# Schematico.net
KiCad netlist of a schematic drawn in EAGLE
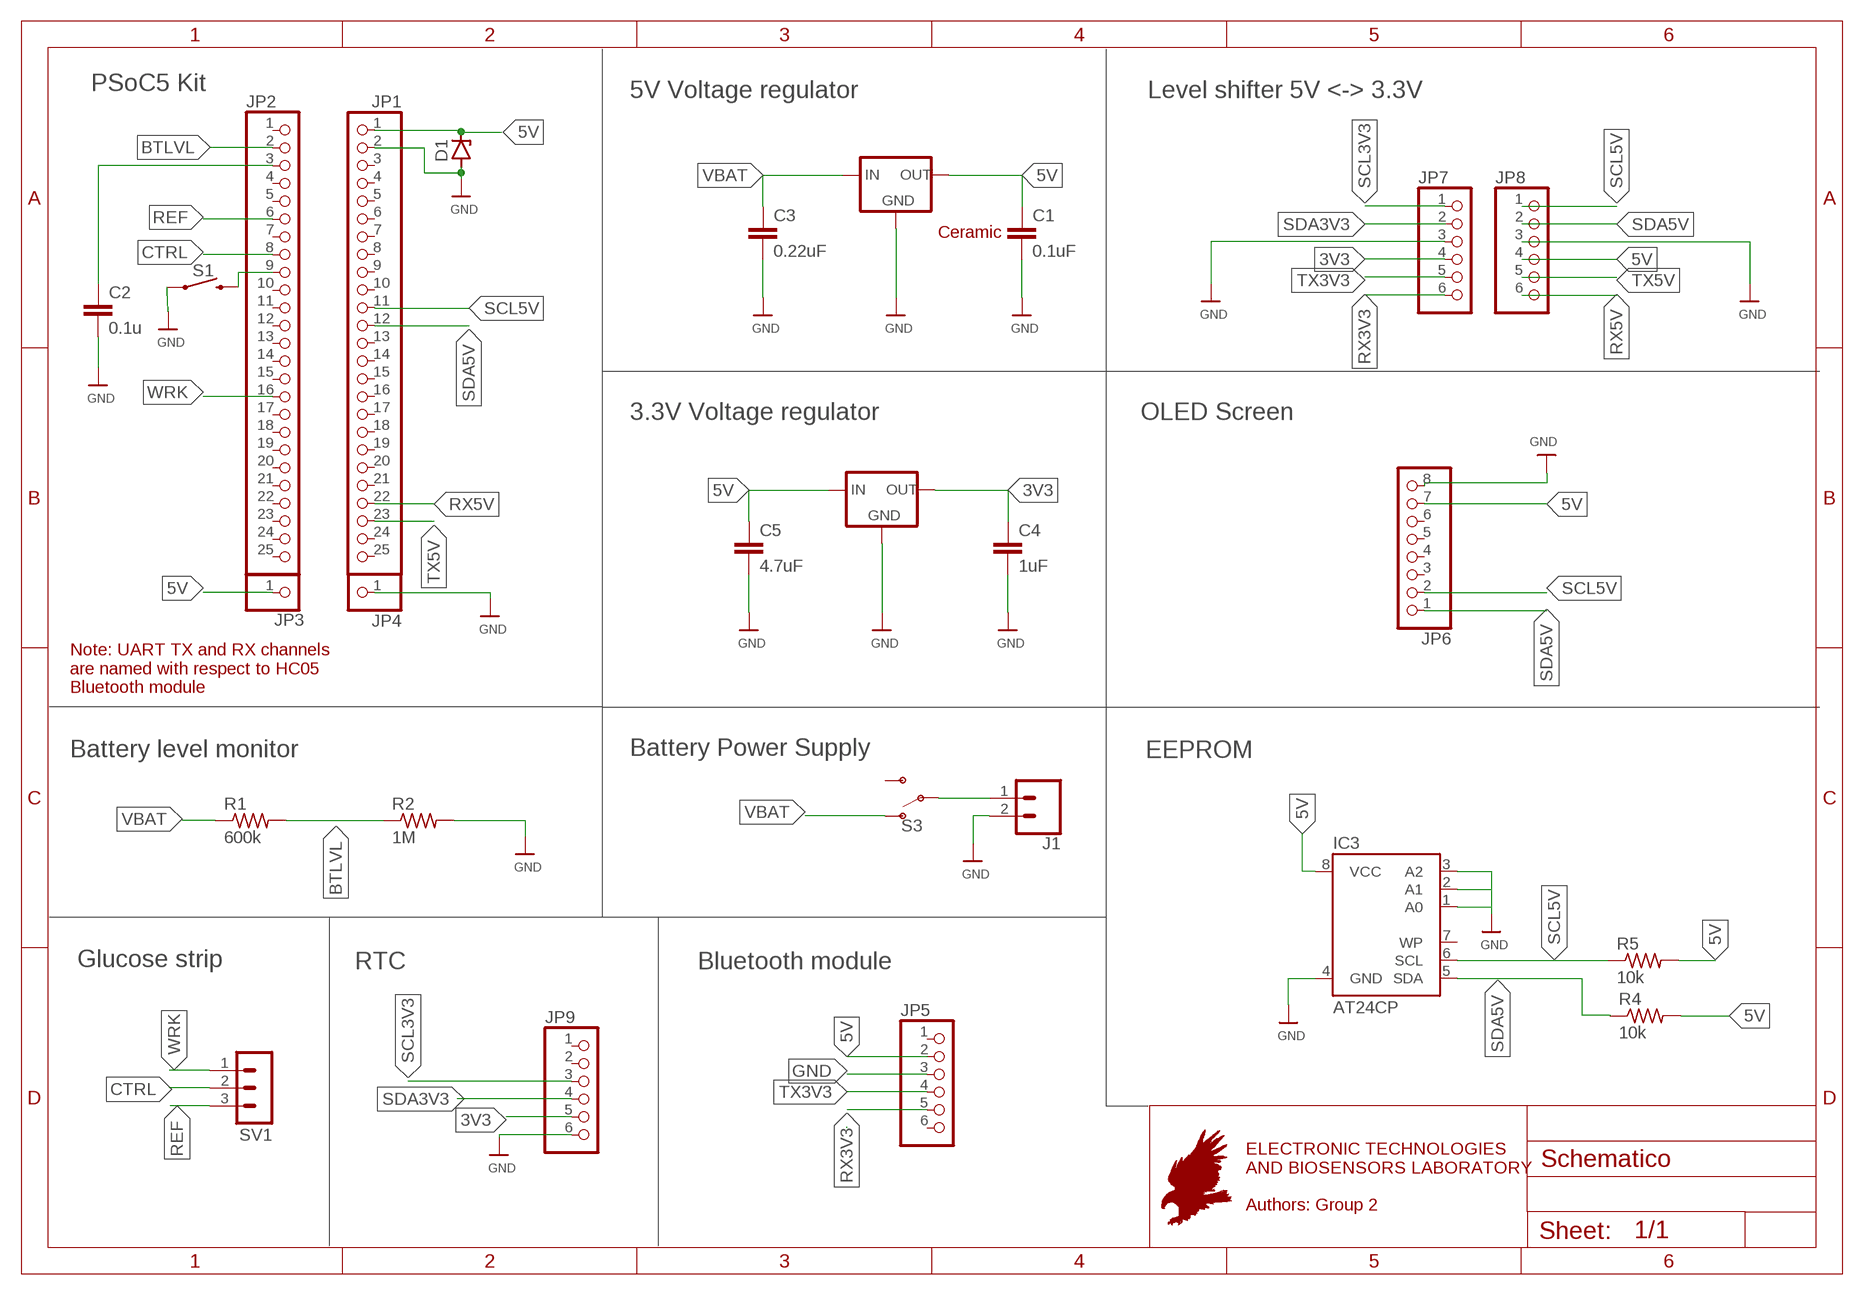
[diagram p0: schematic, sheet 1]

(export (version "E")
  (design (tool "Eeschema 10.0.6"))
  (components
    (comp (ref "C1")
      (value "0.1uF")
      (footprint "eagle-import:C2.5-3")
      (libsource (lib "eagle-import") (part "C2,5-3"))
    )
    (comp (ref "C2")
      (value "0.1u")
      (footprint "eagle-import:C2.5-3")
      (libsource (lib "eagle-import") (part "C2,5-3"))
    )
    (comp (ref "C3")
      (value "0.22uF")
      (footprint "eagle-import:C2.5-3")
      (libsource (lib "eagle-import") (part "C2,5-3"))
    )
    (comp (ref "C4")
      (value "1uF")
      (footprint "eagle-import:C2.5-3")
      (libsource (lib "eagle-import") (part "C2,5-3"))
    )
    (comp (ref "C5")
      (value "4.7uF")
      (footprint "eagle-import:C2.5-3")
      (libsource (lib "eagle-import") (part "C2,5-3"))
    )
    (comp (ref "D1")
      (value "1N821")
      (footprint "eagle-import:DO35Z10")
      (libsource (lib "eagle-import") (part "1N821"))
    )
    (comp (ref "IC1")
      (value "78XXS")
      (footprint "eagle-import:78XXS")
      (libsource (lib "eagle-import") (part "78XXS"))
    )
    (comp (ref "IC2")
      (value "78XXS")
      (footprint "eagle-import:78XXS")
      (libsource (lib "eagle-import") (part "78XXS"))
    )
    (comp (ref "IC3")
      (value "AT24CP")
      (footprint "eagle-import:DIL08")
      (fields (field (name "MPN") "AT24C1024BW-SH-B"))
      (libsource (lib "eagle-import") (part "AT24CP"))
    )
    (comp (ref "J1")
      (value "CONN_02")
      (footprint "eagle-import:1X02")
      (libsource (lib "eagle-import") (part "CONN_02"))
    )
    (comp (ref "JP1")
      (value "PINHD-1X25")
      (footprint "eagle-import:1X25")
      (libsource (lib "eagle-import") (part "PINHD-1X25"))
    )
    (comp (ref "JP2")
      (value "PINHD-1X25")
      (footprint "eagle-import:1X25")
      (libsource (lib "eagle-import") (part "PINHD-1X25"))
    )
    (comp (ref "JP3")
      (value "PINHD-1X1")
      (footprint "eagle-import:1X01")
      (libsource (lib "eagle-import") (part "PINHD-1X1"))
    )
    (comp (ref "JP4")
      (value "PINHD-1X1")
      (footprint "eagle-import:1X01")
      (libsource (lib "eagle-import") (part "PINHD-1X1"))
    )
    (comp (ref "JP5")
      (value "PINHD-1X6B")
      (footprint "eagle-import:1X06-BIG")
      (libsource (lib "eagle-import") (part "PINHD-1X6B"))
    )
    (comp (ref "JP6")
      (value "PINHD-1X8")
      (footprint "eagle-import:1X08")
      (libsource (lib "eagle-import") (part "PINHD-1X8"))
    )
    (comp (ref "JP7")
      (value "PINHD-1X6B")
      (footprint "eagle-import:1X06-BIG")
      (libsource (lib "eagle-import") (part "PINHD-1X6B"))
    )
    (comp (ref "JP8")
      (value "PINHD-1X6B")
      (footprint "eagle-import:1X06-BIG")
      (libsource (lib "eagle-import") (part "PINHD-1X6B"))
    )
    (comp (ref "JP9")
      (value "PINHD-1X6")
      (footprint "eagle-import:1X06")
      (libsource (lib "eagle-import") (part "pinhead_325_PINHD-1X6"))
    )
    (comp (ref "R1")
      (value "600k")
      (footprint "eagle-import:0204_7")
      (libsource (lib "eagle-import") (part "R-US_0204/7"))
    )
    (comp (ref "R2")
      (value "1M")
      (footprint "eagle-import:0204_7")
      (libsource (lib "eagle-import") (part "R-US_0204/7"))
    )
    (comp (ref "R4")
      (value "10k")
      (footprint "eagle-import:0204_7")
      (libsource (lib "eagle-import") (part "R-US_0204/7"))
    )
    (comp (ref "R5")
      (value "10k")
      (footprint "eagle-import:0204_7")
      (libsource (lib "eagle-import") (part "R-US_0204/7"))
    )
    (comp (ref "S1")
      (value "MOMENTARY-SWITCH-SPST-PTH-6.0MM")
      (footprint "eagle-import:TACTILE_SWITCH_PTH_6.0MM")
      (libsource (lib "eagle-import") (part "MOMENTARY-SWITCH-SPST-PTH-6.0MM"))
    )
    (comp (ref "S3")
      (value "SWITCH-SPDT-PTH-11.6X4.0MM")
      (footprint "eagle-import:SWITCH_SPDT_PTH_11.6X4.0MM")
      (libsource (lib "eagle-import") (part "SWITCH-SPDT-PTH-11.6X4.0MM"))
    )
    (comp (ref "SV1")
      (value "MA03-1")
      (footprint "eagle-import:MA03-1")
      (libsource (lib "eagle-import") (part "MA03-1"))
    )
  )
  (nets
    (net (code "1") (name "3V3") (class "Default")
      (node (ref "C4") (pin "1") (pinfunction "1_1") (pintype "passive"))
      (node (ref "IC1") (pin "OUT") (pinfunction "OUT_OUT") (pintype "passive"))
      (node (ref "JP7") (pin "4") (pinfunction "4_4") (pintype "passive"))
      (node (ref "JP9") (pin "5") (pinfunction "5_5") (pintype "passive"))
    )
    (net (code "2") (name "5V") (class "Default")
      (node (ref "C1") (pin "1") (pinfunction "1_1") (pintype "passive"))
      (node (ref "C5") (pin "1") (pinfunction "1_1") (pintype "passive"))
      (node (ref "D1") (pin "C") (pinfunction "C_C") (pintype "passive"))
      (node (ref "IC1") (pin "IN") (pinfunction "IN_IN") (pintype "input"))
      (node (ref "IC2") (pin "OUT") (pinfunction "OUT_OUT") (pintype "passive"))
      (node (ref "IC3") (pin "8") (pinfunction "VCC_8") (pintype "power_in"))
      (node (ref "JP1") (pin "1") (pinfunction "1_1") (pintype "passive"))
      (node (ref "JP3") (pin "1") (pinfunction "1_1") (pintype "passive"))
      (node (ref "JP5") (pin "2") (pinfunction "2_2") (pintype "passive"))
      (node (ref "JP6") (pin "7") (pinfunction "7_7") (pintype "passive"))
      (node (ref "JP8") (pin "4") (pinfunction "4_4") (pintype "passive"))
      (node (ref "R4") (pin "2") (pinfunction "2_2") (pintype "passive"))
      (node (ref "R5") (pin "2") (pinfunction "2_2") (pintype "passive"))
    )
    (net (code "3") (name "BTLVL") (class "Default")
      (node (ref "JP2") (pin "2") (pinfunction "2_2") (pintype "passive"))
      (node (ref "R1") (pin "2") (pinfunction "2_2") (pintype "passive"))
      (node (ref "R2") (pin "1") (pinfunction "1_1") (pintype "passive"))
    )
    (net (code "4") (name "CTRL") (class "Default")
      (node (ref "JP2") (pin "8") (pinfunction "8_8") (pintype "passive"))
      (node (ref "SV1") (pin "2") (pinfunction "2_2") (pintype "passive"))
    )
    (net (code "5") (name "GND") (class "Default")
      (node (ref "C1") (pin "2") (pinfunction "2_2") (pintype "passive"))
      (node (ref "C2") (pin "2") (pinfunction "2_2") (pintype "passive"))
      (node (ref "C3") (pin "2") (pinfunction "2_2") (pintype "passive"))
      (node (ref "C4") (pin "2") (pinfunction "2_2") (pintype "passive"))
      (node (ref "C5") (pin "2") (pinfunction "2_2") (pintype "passive"))
      (node (ref "D1") (pin "A") (pinfunction "A_A") (pintype "passive"))
      (node (ref "IC1") (pin "GND") (pinfunction "GND_GND") (pintype "input"))
      (node (ref "IC2") (pin "GND") (pinfunction "GND_GND") (pintype "input"))
      (node (ref "IC3") (pin "1") (pinfunction "A0_1") (pintype "input"))
      (node (ref "IC3") (pin "2") (pinfunction "A1_2") (pintype "input"))
      (node (ref "IC3") (pin "3") (pinfunction "A2_3") (pintype "input"))
      (node (ref "IC3") (pin "4") (pinfunction "GND_4") (pintype "power_in"))
      (node (ref "J1") (pin "2") (pinfunction "2_2") (pintype "passive"))
      (node (ref "JP1") (pin "2") (pinfunction "2_2") (pintype "passive"))
      (node (ref "JP4") (pin "1") (pinfunction "1_1") (pintype "passive"))
      (node (ref "JP5") (pin "3") (pinfunction "3_3") (pintype "passive"))
      (node (ref "JP6") (pin "8") (pinfunction "8_8") (pintype "passive"))
      (node (ref "JP7") (pin "3") (pinfunction "3_3") (pintype "passive"))
      (node (ref "JP8") (pin "3") (pinfunction "3_3") (pintype "passive"))
      (node (ref "JP9") (pin "6") (pinfunction "6_6") (pintype "passive"))
      (node (ref "R2") (pin "2") (pinfunction "2_2") (pintype "passive"))
      (node (ref "S1") (pin "1") (pinfunction "1_1") (pintype "passive"))
    )
    (net (code "6") (name "Net-(C2-Pad1)") (class "Default")
      (node (ref "C2") (pin "1") (pinfunction "1_1") (pintype "passive"))
      (node (ref "JP2") (pin "3") (pinfunction "3_3") (pintype "passive"))
    )
    (net (code "7") (name "Net-(S1-2)") (class "Default")
      (node (ref "JP2") (pin "9") (pinfunction "9_9") (pintype "passive"))
      (node (ref "S1") (pin "3") (pinfunction "2_3") (pintype "passive"))
    )
    (net (code "8") (name "Net-(S3-P)") (class "Default")
      (node (ref "J1") (pin "1") (pinfunction "1_1") (pintype "passive"))
      (node (ref "S3") (pin "2") (pinfunction "P_2") (pintype "passive"))
    )
    (net (code "9") (name "REF") (class "Default")
      (node (ref "JP2") (pin "6") (pinfunction "6_6") (pintype "passive"))
      (node (ref "SV1") (pin "3") (pinfunction "3_3") (pintype "passive"))
    )
    (net (code "10") (name "RX3V3") (class "Default")
      (node (ref "JP5") (pin "5") (pinfunction "5_5") (pintype "passive"))
      (node (ref "JP7") (pin "6") (pinfunction "6_6") (pintype "passive"))
    )
    (net (code "11") (name "RX5V") (class "Default")
      (node (ref "JP1") (pin "22") (pinfunction "22_22") (pintype "passive"))
      (node (ref "JP8") (pin "6") (pinfunction "6_6") (pintype "passive"))
    )
    (net (code "12") (name "SCL3V3") (class "Default")
      (node (ref "JP7") (pin "1") (pinfunction "1_1") (pintype "passive"))
      (node (ref "JP9") (pin "3") (pinfunction "3_3") (pintype "passive"))
    )
    (net (code "13") (name "SCL5V") (class "Default")
      (node (ref "IC3") (pin "6") (pinfunction "SCL_6") (pintype "bidirectional"))
      (node (ref "JP1") (pin "11") (pinfunction "11_11") (pintype "passive"))
      (node (ref "JP6") (pin "2") (pinfunction "2_2") (pintype "passive"))
      (node (ref "JP8") (pin "1") (pinfunction "1_1") (pintype "passive"))
      (node (ref "R5") (pin "1") (pinfunction "1_1") (pintype "passive"))
    )
    (net (code "14") (name "SDA3V3") (class "Default")
      (node (ref "JP7") (pin "2") (pinfunction "2_2") (pintype "passive"))
      (node (ref "JP9") (pin "4") (pinfunction "4_4") (pintype "passive"))
    )
    (net (code "15") (name "SDA5V") (class "Default")
      (node (ref "IC3") (pin "5") (pinfunction "SDA_5") (pintype "bidirectional"))
      (node (ref "JP1") (pin "12") (pinfunction "12_12") (pintype "passive"))
      (node (ref "JP6") (pin "1") (pinfunction "1_1") (pintype "passive"))
      (node (ref "JP8") (pin "2") (pinfunction "2_2") (pintype "passive"))
      (node (ref "R4") (pin "1") (pinfunction "1_1") (pintype "passive"))
    )
    (net (code "16") (name "TX3V3") (class "Default")
      (node (ref "JP5") (pin "4") (pinfunction "4_4") (pintype "passive"))
      (node (ref "JP7") (pin "5") (pinfunction "5_5") (pintype "passive"))
    )
    (net (code "17") (name "TX5V") (class "Default")
      (node (ref "JP1") (pin "23") (pinfunction "23_23") (pintype "passive"))
      (node (ref "JP8") (pin "5") (pinfunction "5_5") (pintype "passive"))
    )
    (net (code "18") (name "VBAT") (class "Default")
      (node (ref "C3") (pin "1") (pinfunction "1_1") (pintype "passive"))
      (node (ref "IC2") (pin "IN") (pinfunction "IN_IN") (pintype "input"))
      (node (ref "R1") (pin "1") (pinfunction "1_1") (pintype "passive"))
      (node (ref "S3") (pin "1") (pinfunction "O_1") (pintype "passive"))
    )
    (net (code "19") (name "WRK") (class "Default")
      (node (ref "JP2") (pin "16") (pinfunction "16_16") (pintype "passive"))
      (node (ref "SV1") (pin "1") (pinfunction "1_1") (pintype "passive"))
    )
    (net (code "20") (name "unconnected-(IC3-WP-Pad7)") (class "Default")
      (node (ref "IC3") (pin "7") (pinfunction "WP_7") (pintype "input"))
    )
    (net (code "21") (name "unconnected-(JP1-Pad3)") (class "Default")
      (node (ref "JP1") (pin "3") (pinfunction "3_3") (pintype "passive"))
    )
    (net (code "22") (name "unconnected-(JP1-Pad4)") (class "Default")
      (node (ref "JP1") (pin "4") (pinfunction "4_4") (pintype "passive"))
    )
    (net (code "23") (name "unconnected-(JP1-Pad5)") (class "Default")
      (node (ref "JP1") (pin "5") (pinfunction "5_5") (pintype "passive"))
    )
    (net (code "24") (name "unconnected-(JP1-Pad6)") (class "Default")
      (node (ref "JP1") (pin "6") (pinfunction "6_6") (pintype "passive"))
    )
    (net (code "25") (name "unconnected-(JP1-Pad7)") (class "Default")
      (node (ref "JP1") (pin "7") (pinfunction "7_7") (pintype "passive"))
    )
    (net (code "26") (name "unconnected-(JP1-Pad8)") (class "Default")
      (node (ref "JP1") (pin "8") (pinfunction "8_8") (pintype "passive"))
    )
    (net (code "27") (name "unconnected-(JP1-Pad9)") (class "Default")
      (node (ref "JP1") (pin "9") (pinfunction "9_9") (pintype "passive"))
    )
    (net (code "28") (name "unconnected-(JP1-Pad10)") (class "Default")
      (node (ref "JP1") (pin "10") (pinfunction "10_10") (pintype "passive"))
    )
    (net (code "29") (name "unconnected-(JP1-Pad13)") (class "Default")
      (node (ref "JP1") (pin "13") (pinfunction "13_13") (pintype "passive"))
    )
    (net (code "30") (name "unconnected-(JP1-Pad14)") (class "Default")
      (node (ref "JP1") (pin "14") (pinfunction "14_14") (pintype "passive"))
    )
    (net (code "31") (name "unconnected-(JP1-Pad15)") (class "Default")
      (node (ref "JP1") (pin "15") (pinfunction "15_15") (pintype "passive"))
    )
    (net (code "32") (name "unconnected-(JP1-Pad16)") (class "Default")
      (node (ref "JP1") (pin "16") (pinfunction "16_16") (pintype "passive"))
    )
    (net (code "33") (name "unconnected-(JP1-Pad17)") (class "Default")
      (node (ref "JP1") (pin "17") (pinfunction "17_17") (pintype "passive"))
    )
    (net (code "34") (name "unconnected-(JP1-Pad18)") (class "Default")
      (node (ref "JP1") (pin "18") (pinfunction "18_18") (pintype "passive"))
    )
    (net (code "35") (name "unconnected-(JP1-Pad19)") (class "Default")
      (node (ref "JP1") (pin "19") (pinfunction "19_19") (pintype "passive"))
    )
    (net (code "36") (name "unconnected-(JP1-Pad20)") (class "Default")
      (node (ref "JP1") (pin "20") (pinfunction "20_20") (pintype "passive"))
    )
    (net (code "37") (name "unconnected-(JP1-Pad21)") (class "Default")
      (node (ref "JP1") (pin "21") (pinfunction "21_21") (pintype "passive"))
    )
    (net (code "38") (name "unconnected-(JP1-Pad24)") (class "Default")
      (node (ref "JP1") (pin "24") (pinfunction "24_24") (pintype "passive"))
    )
    (net (code "39") (name "unconnected-(JP1-Pad25)") (class "Default")
      (node (ref "JP1") (pin "25") (pinfunction "25_25") (pintype "passive"))
    )
    (net (code "40") (name "unconnected-(JP2-Pad1)") (class "Default")
      (node (ref "JP2") (pin "1") (pinfunction "1_1") (pintype "passive"))
    )
    (net (code "41") (name "unconnected-(JP2-Pad4)") (class "Default")
      (node (ref "JP2") (pin "4") (pinfunction "4_4") (pintype "passive"))
    )
    (net (code "42") (name "unconnected-(JP2-Pad5)") (class "Default")
      (node (ref "JP2") (pin "5") (pinfunction "5_5") (pintype "passive"))
    )
    (net (code "43") (name "unconnected-(JP2-Pad7)") (class "Default")
      (node (ref "JP2") (pin "7") (pinfunction "7_7") (pintype "passive"))
    )
    (net (code "44") (name "unconnected-(JP2-Pad10)") (class "Default")
      (node (ref "JP2") (pin "10") (pinfunction "10_10") (pintype "passive"))
    )
    (net (code "45") (name "unconnected-(JP2-Pad11)") (class "Default")
      (node (ref "JP2") (pin "11") (pinfunction "11_11") (pintype "passive"))
    )
    (net (code "46") (name "unconnected-(JP2-Pad12)") (class "Default")
      (node (ref "JP2") (pin "12") (pinfunction "12_12") (pintype "passive"))
    )
    (net (code "47") (name "unconnected-(JP2-Pad13)") (class "Default")
      (node (ref "JP2") (pin "13") (pinfunction "13_13") (pintype "passive"))
    )
    (net (code "48") (name "unconnected-(JP2-Pad14)") (class "Default")
      (node (ref "JP2") (pin "14") (pinfunction "14_14") (pintype "passive"))
    )
    (net (code "49") (name "unconnected-(JP2-Pad15)") (class "Default")
      (node (ref "JP2") (pin "15") (pinfunction "15_15") (pintype "passive"))
    )
    (net (code "50") (name "unconnected-(JP2-Pad17)") (class "Default")
      (node (ref "JP2") (pin "17") (pinfunction "17_17") (pintype "passive"))
    )
    (net (code "51") (name "unconnected-(JP2-Pad18)") (class "Default")
      (node (ref "JP2") (pin "18") (pinfunction "18_18") (pintype "passive"))
    )
    (net (code "52") (name "unconnected-(JP2-Pad19)") (class "Default")
      (node (ref "JP2") (pin "19") (pinfunction "19_19") (pintype "passive"))
    )
    (net (code "53") (name "unconnected-(JP2-Pad20)") (class "Default")
      (node (ref "JP2") (pin "20") (pinfunction "20_20") (pintype "passive"))
    )
    (net (code "54") (name "unconnected-(JP2-Pad21)") (class "Default")
      (node (ref "JP2") (pin "21") (pinfunction "21_21") (pintype "passive"))
    )
    (net (code "55") (name "unconnected-(JP2-Pad22)") (class "Default")
      (node (ref "JP2") (pin "22") (pinfunction "22_22") (pintype "passive"))
    )
    (net (code "56") (name "unconnected-(JP2-Pad23)") (class "Default")
      (node (ref "JP2") (pin "23") (pinfunction "23_23") (pintype "passive"))
    )
    (net (code "57") (name "unconnected-(JP2-Pad24)") (class "Default")
      (node (ref "JP2") (pin "24") (pinfunction "24_24") (pintype "passive"))
    )
    (net (code "58") (name "unconnected-(JP2-Pad25)") (class "Default")
      (node (ref "JP2") (pin "25") (pinfunction "25_25") (pintype "passive"))
    )
    (net (code "59") (name "unconnected-(JP5-Pad1)") (class "Default")
      (node (ref "JP5") (pin "1") (pinfunction "1_1") (pintype "passive"))
    )
    (net (code "60") (name "unconnected-(JP5-Pad6)") (class "Default")
      (node (ref "JP5") (pin "6") (pinfunction "6_6") (pintype "passive"))
    )
    (net (code "61") (name "unconnected-(JP6-Pad3)") (class "Default")
      (node (ref "JP6") (pin "3") (pinfunction "3_3") (pintype "passive"))
    )
    (net (code "62") (name "unconnected-(JP6-Pad4)") (class "Default")
      (node (ref "JP6") (pin "4") (pinfunction "4_4") (pintype "passive"))
    )
    (net (code "63") (name "unconnected-(JP6-Pad5)") (class "Default")
      (node (ref "JP6") (pin "5") (pinfunction "5_5") (pintype "passive"))
    )
    (net (code "64") (name "unconnected-(JP6-Pad6)") (class "Default")
      (node (ref "JP6") (pin "6") (pinfunction "6_6") (pintype "passive"))
    )
    (net (code "65") (name "unconnected-(JP9-Pad1)") (class "Default")
      (node (ref "JP9") (pin "1") (pinfunction "1_1") (pintype "passive"))
    )
    (net (code "66") (name "unconnected-(JP9-Pad2)") (class "Default")
      (node (ref "JP9") (pin "2") (pinfunction "2_2") (pintype "passive"))
    )
    (net (code "67") (name "unconnected-(S3-S-Pad3)") (class "Default")
      (node (ref "S3") (pin "3") (pinfunction "S_3") (pintype "passive"))
    )
  )
)
